# REG_top.net
KiCad netlist of a schematic drawn in Altium Designer
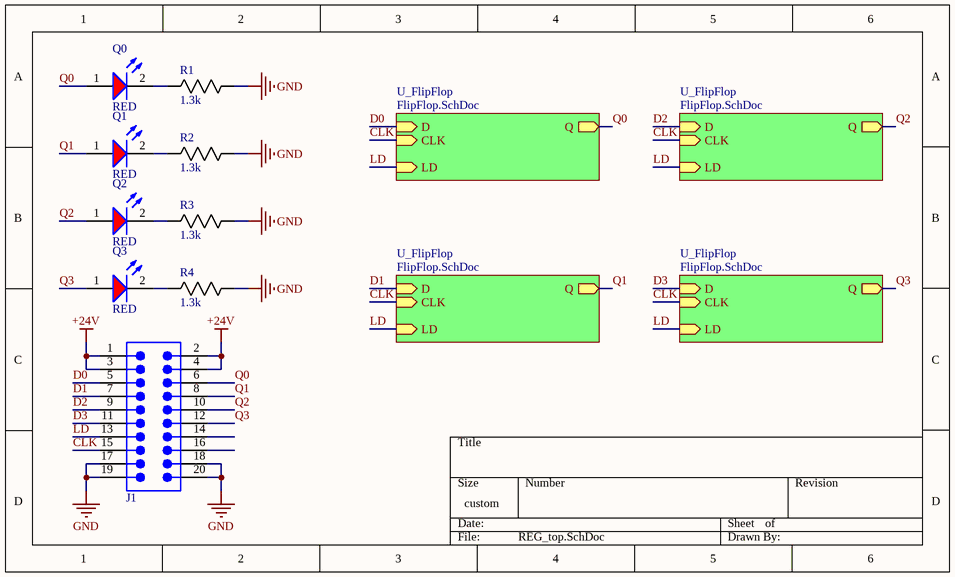
[diagram p0: REG_top.SchDoc]

(export (version "E")
  (design (tool "Eeschema 10.0.6"))
  (components
    (comp (ref "J1")
      (value "Con 2.54mm 10x2pos")
      (footprint "Con 2.54mm 10x2pos")
      (description "WR-BHD Straight Male, Box Header, Through Hole, 2 Rows, 20 Contacts, 2.54mm Pitch")
      (fields
        (field (name "MANUFACTURER") "Wurth Elektronik")
        (field (name "MANUFACTURER PART NUMBER") "61202021621")
      )
      (libsource (lib "RelayMachine") (part "Con 2.54mm 10x2pos"))
    )
    (comp (ref "Q0")
      (value "RED")
      (footprint "LED RED 151051RS11000")
      (description "WL-TMRC Red Color Diffused 5 mm Round Through Hole LED")
      (fields
        (field (name "MANUFACTURER") "Wurth Elektronik")
        (field (name "MANUFACTURER PART NUMBER") "151051RS11000")
      )
      (libsource (lib "Schlib1") (part "LED RED 151051RS11000"))
    )
    (comp (ref "Q1")
      (value "RED")
      (footprint "LED RED 151051RS11000")
      (description "WL-TMRC Red Color Diffused 5 mm Round Through Hole LED")
      (fields
        (field (name "MANUFACTURER") "Wurth Elektronik")
        (field (name "MANUFACTURER PART NUMBER") "151051RS11000")
      )
      (libsource (lib "Schlib1") (part "LED RED 151051RS11000"))
    )
    (comp (ref "Q2")
      (value "RED")
      (footprint "LED RED 151051RS11000")
      (description "WL-TMRC Red Color Diffused 5 mm Round Through Hole LED")
      (fields
        (field (name "MANUFACTURER") "Wurth Elektronik")
        (field (name "MANUFACTURER PART NUMBER") "151051RS11000")
      )
      (libsource (lib "Schlib1") (part "LED RED 151051RS11000"))
    )
    (comp (ref "Q3")
      (value "RED")
      (footprint "LED RED 151051RS11000")
      (description "WL-TMRC Red Color Diffused 5 mm Round Through Hole LED")
      (fields
        (field (name "MANUFACTURER") "Wurth Elektronik")
        (field (name "MANUFACTURER PART NUMBER") "151051RS11000")
      )
      (libsource (lib "Schlib1") (part "LED RED 151051RS11000"))
    )
    (comp (ref "R1")
      (value "1.3k")
      (footprint "RES 2512")
      (description "Res Thick Film 2512 1.3K Ohm 1% 1W ±100ppm/C Pad SMD Automotive T/R RMCF2512FT1K30")
      (fields
        (field (name "MANUFACTURER") "Stackpole Electronics")
        (field (name "MANUFACTURER PART NUMBER") "RMCF2512FT1K30")
      )
      (libsource (lib "Schlib1") (part "RES 1.3k 2512 1W"))
    )
    (comp (ref "R2")
      (value "1.3k")
      (footprint "RES 2512")
      (description "Res Thick Film 2512 1.3K Ohm 1% 1W ±100ppm/C Pad SMD Automotive T/R RMCF2512FT1K30")
      (fields
        (field (name "MANUFACTURER") "Stackpole Electronics")
        (field (name "MANUFACTURER PART NUMBER") "RMCF2512FT1K30")
      )
      (libsource (lib "Schlib1") (part "RES 1.3k 2512 1W"))
    )
    (comp (ref "R3")
      (value "1.3k")
      (footprint "RES 2512")
      (description "Res Thick Film 2512 1.3K Ohm 1% 1W ±100ppm/C Pad SMD Automotive T/R RMCF2512FT1K30")
      (fields
        (field (name "MANUFACTURER") "Stackpole Electronics")
        (field (name "MANUFACTURER PART NUMBER") "RMCF2512FT1K30")
      )
      (libsource (lib "Schlib1") (part "RES 1.3k 2512 1W"))
    )
    (comp (ref "R4")
      (value "1.3k")
      (footprint "RES 2512")
      (description "Res Thick Film 2512 1.3K Ohm 1% 1W ±100ppm/C Pad SMD Automotive T/R RMCF2512FT1K30")
      (fields
        (field (name "MANUFACTURER") "Stackpole Electronics")
        (field (name "MANUFACTURER PART NUMBER") "RMCF2512FT1K30")
      )
      (libsource (lib "Schlib1") (part "RES 1.3k 2512 1W"))
    )
  )
  (nets
    (net (code "1") (name "+24V") (class "Default")
      (node (ref "J1") (pin "1") (pinfunction "1_1") (pintype "passive"))
      (node (ref "J1") (pin "2") (pinfunction "2_2") (pintype "passive"))
      (node (ref "J1") (pin "3") (pinfunction "3_3") (pintype "passive"))
      (node (ref "J1") (pin "4") (pinfunction "4_4") (pintype "passive"))
    )
    (net (code "2") (name "/CLK") (class "Default")
      (node (ref "J1") (pin "15") (pinfunction "15_15") (pintype "passive"))
    )
    (net (code "3") (name "/D0") (class "Default")
      (node (ref "J1") (pin "5") (pinfunction "5_5") (pintype "passive"))
    )
    (net (code "4") (name "/D1") (class "Default")
      (node (ref "J1") (pin "7") (pinfunction "7_7") (pintype "passive"))
    )
    (net (code "5") (name "/D2") (class "Default")
      (node (ref "J1") (pin "9") (pinfunction "9_9") (pintype "passive"))
    )
    (net (code "6") (name "/D3") (class "Default")
      (node (ref "J1") (pin "11") (pinfunction "11_11") (pintype "passive"))
    )
    (net (code "7") (name "/LD") (class "Default")
      (node (ref "J1") (pin "13") (pinfunction "13_13") (pintype "passive"))
    )
    (net (code "8") (name "/Q0") (class "Default")
      (node (ref "J1") (pin "6") (pinfunction "6_6") (pintype "passive"))
      (node (ref "Q0") (pin "1") (pinfunction "A_1") (pintype "passive"))
    )
    (net (code "9") (name "/Q1") (class "Default")
      (node (ref "J1") (pin "8") (pinfunction "8_8") (pintype "passive"))
      (node (ref "Q1") (pin "1") (pinfunction "A_1") (pintype "passive"))
    )
    (net (code "10") (name "/Q2") (class "Default")
      (node (ref "J1") (pin "10") (pinfunction "10_10") (pintype "passive"))
      (node (ref "Q2") (pin "1") (pinfunction "A_1") (pintype "passive"))
    )
    (net (code "11") (name "/Q3") (class "Default")
      (node (ref "J1") (pin "12") (pinfunction "12_12") (pintype "passive"))
      (node (ref "Q3") (pin "1") (pinfunction "A_1") (pintype "passive"))
    )
    (net (code "12") (name "GND") (class "Default")
      (node (ref "J1") (pin "17") (pinfunction "17_17") (pintype "passive"))
      (node (ref "J1") (pin "18") (pinfunction "18_18") (pintype "passive"))
      (node (ref "J1") (pin "19") (pinfunction "19_19") (pintype "passive"))
      (node (ref "J1") (pin "20") (pinfunction "20_20") (pintype "passive"))
      (node (ref "R1") (pin "2") (pinfunction "2_2") (pintype "passive"))
      (node (ref "R2") (pin "2") (pinfunction "2_2") (pintype "passive"))
      (node (ref "R3") (pin "2") (pinfunction "2_2") (pintype "passive"))
      (node (ref "R4") (pin "2") (pinfunction "2_2") (pintype "passive"))
    )
    (net (code "13") (name "Net-(Q0-K)") (class "Default")
      (node (ref "Q0") (pin "2") (pinfunction "K_2") (pintype "passive"))
      (node (ref "R1") (pin "1") (pinfunction "1_1") (pintype "passive"))
    )
    (net (code "14") (name "Net-(Q1-K)") (class "Default")
      (node (ref "Q1") (pin "2") (pinfunction "K_2") (pintype "passive"))
      (node (ref "R2") (pin "1") (pinfunction "1_1") (pintype "passive"))
    )
    (net (code "15") (name "Net-(Q2-K)") (class "Default")
      (node (ref "Q2") (pin "2") (pinfunction "K_2") (pintype "passive"))
      (node (ref "R3") (pin "1") (pinfunction "1_1") (pintype "passive"))
    )
    (net (code "16") (name "Net-(Q3-K)") (class "Default")
      (node (ref "Q3") (pin "2") (pinfunction "K_2") (pintype "passive"))
      (node (ref "R4") (pin "1") (pinfunction "1_1") (pintype "passive"))
    )
    (net (code "17") (name "unconnected-(J1-Pad14)") (class "Default")
      (node (ref "J1") (pin "14") (pinfunction "14_14") (pintype "passive"))
    )
    (net (code "18") (name "unconnected-(J1-Pad16)") (class "Default")
      (node (ref "J1") (pin "16") (pinfunction "16_16") (pintype "passive"))
    )
  )
)
